# MPPC_amp.net
KiCad netlist of a schematic drawn in EAGLE
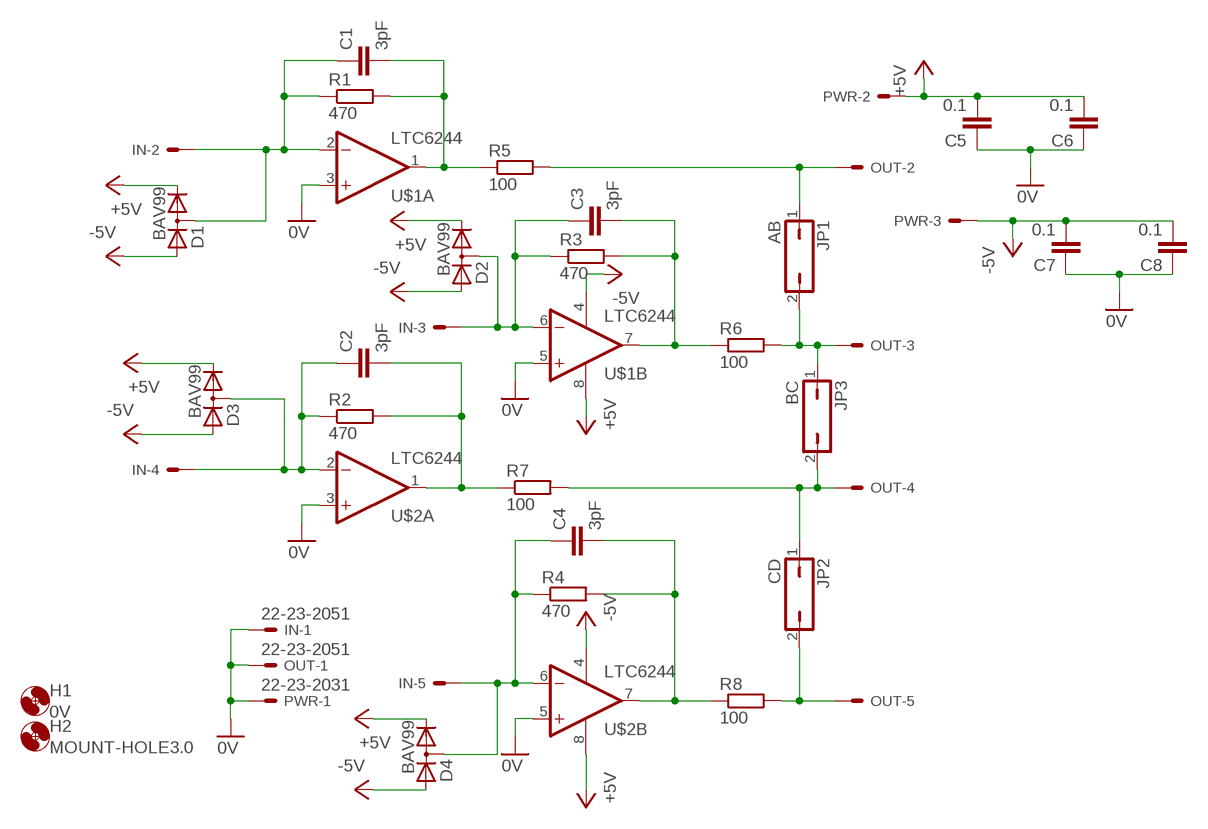
[diagram p0: schematic, sheet 1]

(export (version "E")
  (design (tool "Eeschema 10.0.6"))
  (components
    (comp (ref "C1")
      (value "3pF")
      (footprint "eagle-import:C0805")
      (libsource (lib "eagle-import") (part "C-EUC0805"))
    )
    (comp (ref "C2")
      (value "3pF")
      (footprint "eagle-import:C0805")
      (libsource (lib "eagle-import") (part "C-EUC0805"))
    )
    (comp (ref "C3")
      (value "3pF")
      (footprint "eagle-import:C0805")
      (libsource (lib "eagle-import") (part "C-EUC0805"))
    )
    (comp (ref "C4")
      (value "3pF")
      (footprint "eagle-import:C0805")
      (libsource (lib "eagle-import") (part "C-EUC0805"))
    )
    (comp (ref "C5")
      (value "0.1")
      (footprint "eagle-import:C0805")
      (libsource (lib "eagle-import") (part "C-EUC0805"))
    )
    (comp (ref "C6")
      (value "0.1")
      (footprint "eagle-import:C0805")
      (libsource (lib "eagle-import") (part "C-EUC0805"))
    )
    (comp (ref "C7")
      (value "0.1")
      (footprint "eagle-import:C0805")
      (libsource (lib "eagle-import") (part "C-EUC0805"))
    )
    (comp (ref "C8")
      (value "0.1")
      (footprint "eagle-import:C0805")
      (libsource (lib "eagle-import") (part "C-EUC0805"))
    )
    (comp (ref "D1")
      (value "BAV99")
      (footprint "eagle-import:SOT23")
      (libsource (lib "eagle-import") (part "BAV99"))
    )
    (comp (ref "D2")
      (value "BAV99")
      (footprint "eagle-import:SOT23")
      (libsource (lib "eagle-import") (part "BAV99"))
    )
    (comp (ref "D3")
      (value "BAV99")
      (footprint "eagle-import:SOT23")
      (libsource (lib "eagle-import") (part "BAV99"))
    )
    (comp (ref "D4")
      (value "BAV99")
      (footprint "eagle-import:SOT23")
      (libsource (lib "eagle-import") (part "BAV99"))
    )
    (comp (ref "H1")
      (value "0V")
      (footprint "eagle-import:3,0")
      (libsource (lib "eagle-import") (part "MOUNT-HOLE3.0"))
    )
    (comp (ref "H2")
      (value "MOUNT-HOLE3.0")
      (footprint "eagle-import:3,0")
      (libsource (lib "eagle-import") (part "MOUNT-HOLE3.0"))
    )
    (comp (ref "IN")
      (value "22-23-2051")
      (footprint "eagle-import:22-23-2051")
      (fields (field (name "MF") "MOLEX"))
      (libsource (lib "eagle-import") (part "22-23-2051"))
    )
    (comp (ref "JP1")
      (value "AB")
      (footprint "eagle-import:JP1")
      (libsource (lib "eagle-import") (part "JP1Q"))
    )
    (comp (ref "JP2")
      (value "CD")
      (footprint "eagle-import:JP1")
      (libsource (lib "eagle-import") (part "JP1Q"))
    )
    (comp (ref "JP3")
      (value "BC")
      (footprint "eagle-import:JP1")
      (libsource (lib "eagle-import") (part "JP1Q"))
    )
    (comp (ref "OUT")
      (value "22-23-2051")
      (footprint "eagle-import:22-23-2051")
      (fields (field (name "MF") "MOLEX"))
      (libsource (lib "eagle-import") (part "22-23-2051"))
    )
    (comp (ref "PWR")
      (value "22-23-2031")
      (footprint "eagle-import:22-23-2031")
      (fields (field (name "MF") "MOLEX"))
      (libsource (lib "eagle-import") (part "22-23-2031"))
    )
    (comp (ref "R1")
      (value "470")
      (footprint "eagle-import:R0805")
      (libsource (lib "eagle-import") (part "R-EU_R0805"))
    )
    (comp (ref "R2")
      (value "470")
      (footprint "eagle-import:R0805")
      (libsource (lib "eagle-import") (part "R-EU_R0805"))
    )
    (comp (ref "R3")
      (value "470")
      (footprint "eagle-import:R0805")
      (libsource (lib "eagle-import") (part "R-EU_R0805"))
    )
    (comp (ref "R4")
      (value "470")
      (footprint "eagle-import:R0805")
      (libsource (lib "eagle-import") (part "R-EU_R0805"))
    )
    (comp (ref "R5")
      (value "100")
      (footprint "eagle-import:R0805")
      (libsource (lib "eagle-import") (part "R-EU_R0805"))
    )
    (comp (ref "R6")
      (value "100")
      (footprint "eagle-import:R0805")
      (libsource (lib "eagle-import") (part "R-EU_R0805"))
    )
    (comp (ref "R7")
      (value "100")
      (footprint "eagle-import:R0805")
      (libsource (lib "eagle-import") (part "R-EU_R0805"))
    )
    (comp (ref "R8")
      (value "100")
      (footprint "eagle-import:R0805")
      (libsource (lib "eagle-import") (part "R-EU_R0805"))
    )
    (comp (ref "U$1")
      (value "LTC6244")
      (footprint "eagle-import:MSOP08")
      (libsource (lib "eagle-import") (part "LTC6244"))
    )
    (comp (ref "U$2")
      (value "LTC6244")
      (footprint "eagle-import:MSOP08")
      (libsource (lib "eagle-import") (part "LTC6244"))
    )
  )
  (nets
    (net (code "1") (name "+5V") (class "Default")
      (node (ref "C5") (pin "2") (pinfunction "2_2") (pintype "passive"))
      (node (ref "C6") (pin "2") (pinfunction "2_2") (pintype "passive"))
      (node (ref "D1") (pin "2") (pinfunction "C_2") (pintype "passive"))
      (node (ref "D2") (pin "2") (pinfunction "C_2") (pintype "passive"))
      (node (ref "D3") (pin "2") (pinfunction "C_2") (pintype "passive"))
      (node (ref "D4") (pin "2") (pinfunction "C_2") (pintype "passive"))
      (node (ref "PWR") (pin "2") (pinfunction "S_2") (pintype "passive"))
      (node (ref "U$1") (pin "8") (pinfunction "V+_8") (pintype "power_in"))
      (node (ref "U$2") (pin "8") (pinfunction "V+_8") (pintype "power_in"))
    )
    (net (code "2") (name "-5V") (class "Default")
      (node (ref "C7") (pin "2") (pinfunction "2_2") (pintype "passive"))
      (node (ref "C8") (pin "2") (pinfunction "2_2") (pintype "passive"))
      (node (ref "D1") (pin "1") (pinfunction "A_1") (pintype "passive"))
      (node (ref "D2") (pin "1") (pinfunction "A_1") (pintype "passive"))
      (node (ref "D3") (pin "1") (pinfunction "A_1") (pintype "passive"))
      (node (ref "D4") (pin "1") (pinfunction "A_1") (pintype "passive"))
      (node (ref "PWR") (pin "3") (pinfunction "S_3") (pintype "passive"))
      (node (ref "U$1") (pin "4") (pinfunction "V-_4") (pintype "power_in"))
      (node (ref "U$2") (pin "4") (pinfunction "V-_4") (pintype "power_in"))
    )
    (net (code "3") (name "0V") (class "Default")
      (node (ref "C5") (pin "1") (pinfunction "1_1") (pintype "passive"))
      (node (ref "C6") (pin "1") (pinfunction "1_1") (pintype "passive"))
      (node (ref "C7") (pin "1") (pinfunction "1_1") (pintype "passive"))
      (node (ref "C8") (pin "1") (pinfunction "1_1") (pintype "passive"))
      (node (ref "IN") (pin "1") (pinfunction "S_1") (pintype "passive"))
      (node (ref "OUT") (pin "1") (pinfunction "S_1") (pintype "passive"))
      (node (ref "PWR") (pin "1") (pinfunction "S_1") (pintype "passive"))
      (node (ref "U$1") (pin "3") (pinfunction "+IN_3") (pintype "input"))
      (node (ref "U$1") (pin "5") (pinfunction "+IN_5") (pintype "input"))
      (node (ref "U$2") (pin "3") (pinfunction "+IN_3") (pintype "input"))
      (node (ref "U$2") (pin "5") (pinfunction "+IN_5") (pintype "input"))
    )
    (net (code "4") (name "Net-(D1-AC)") (class "Default")
      (node (ref "C1") (pin "1") (pinfunction "1_1") (pintype "passive"))
      (node (ref "D1") (pin "3") (pinfunction "AC_3") (pintype "passive"))
      (node (ref "IN") (pin "2") (pinfunction "S_2") (pintype "passive"))
      (node (ref "R1") (pin "1") (pinfunction "1_1") (pintype "passive"))
      (node (ref "U$1") (pin "2") (pinfunction "-IN_2") (pintype "input"))
    )
    (net (code "5") (name "Net-(D2-AC)") (class "Default")
      (node (ref "C3") (pin "1") (pinfunction "1_1") (pintype "passive"))
      (node (ref "D2") (pin "3") (pinfunction "AC_3") (pintype "passive"))
      (node (ref "IN") (pin "3") (pinfunction "S_3") (pintype "passive"))
      (node (ref "R3") (pin "1") (pinfunction "1_1") (pintype "passive"))
      (node (ref "U$1") (pin "6") (pinfunction "-IN_6") (pintype "input"))
    )
    (net (code "6") (name "Net-(D3-AC)") (class "Default")
      (node (ref "C2") (pin "1") (pinfunction "1_1") (pintype "passive"))
      (node (ref "D3") (pin "3") (pinfunction "AC_3") (pintype "passive"))
      (node (ref "IN") (pin "4") (pinfunction "S_4") (pintype "passive"))
      (node (ref "R2") (pin "1") (pinfunction "1_1") (pintype "passive"))
      (node (ref "U$2") (pin "2") (pinfunction "-IN_2") (pintype "input"))
    )
    (net (code "7") (name "Net-(D4-AC)") (class "Default")
      (node (ref "C4") (pin "1") (pinfunction "1_1") (pintype "passive"))
      (node (ref "D4") (pin "3") (pinfunction "AC_3") (pintype "passive"))
      (node (ref "IN") (pin "5") (pinfunction "S_5") (pintype "passive"))
      (node (ref "R4") (pin "1") (pinfunction "1_1") (pintype "passive"))
      (node (ref "U$2") (pin "6") (pinfunction "-IN_6") (pintype "input"))
    )
    (net (code "8") (name "Net-(OUTB-S)") (class "Default")
      (node (ref "JP1") (pin "1") (pinfunction "1_1") (pintype "passive"))
      (node (ref "OUT") (pin "2") (pinfunction "S_2") (pintype "passive"))
      (node (ref "R5") (pin "2") (pinfunction "2_2") (pintype "passive"))
    )
    (net (code "9") (name "Net-(OUTC-S)") (class "Default")
      (node (ref "JP1") (pin "2") (pinfunction "2_2") (pintype "passive"))
      (node (ref "JP3") (pin "1") (pinfunction "1_1") (pintype "passive"))
      (node (ref "OUT") (pin "3") (pinfunction "S_3") (pintype "passive"))
      (node (ref "R6") (pin "2") (pinfunction "2_2") (pintype "passive"))
    )
    (net (code "10") (name "Net-(OUTD-S)") (class "Default")
      (node (ref "JP2") (pin "1") (pinfunction "1_1") (pintype "passive"))
      (node (ref "JP3") (pin "2") (pinfunction "2_2") (pintype "passive"))
      (node (ref "OUT") (pin "4") (pinfunction "S_4") (pintype "passive"))
      (node (ref "R7") (pin "2") (pinfunction "2_2") (pintype "passive"))
    )
    (net (code "11") (name "Net-(OUTE-S)") (class "Default")
      (node (ref "JP2") (pin "2") (pinfunction "2_2") (pintype "passive"))
      (node (ref "OUT") (pin "5") (pinfunction "S_5") (pintype "passive"))
      (node (ref "R8") (pin "2") (pinfunction "2_2") (pintype "passive"))
    )
    (net (code "12") (name "Net-(U$1A-OUT)") (class "Default")
      (node (ref "C1") (pin "2") (pinfunction "2_2") (pintype "passive"))
      (node (ref "R1") (pin "2") (pinfunction "2_2") (pintype "passive"))
      (node (ref "R5") (pin "1") (pinfunction "1_1") (pintype "passive"))
      (node (ref "U$1") (pin "1") (pinfunction "OUT_1") (pintype "output"))
    )
    (net (code "13") (name "Net-(U$1B-OUT)") (class "Default")
      (node (ref "C3") (pin "2") (pinfunction "2_2") (pintype "passive"))
      (node (ref "R3") (pin "2") (pinfunction "2_2") (pintype "passive"))
      (node (ref "R6") (pin "1") (pinfunction "1_1") (pintype "passive"))
      (node (ref "U$1") (pin "7") (pinfunction "OUT_7") (pintype "output"))
    )
    (net (code "14") (name "Net-(U$2A-OUT)") (class "Default")
      (node (ref "C2") (pin "2") (pinfunction "2_2") (pintype "passive"))
      (node (ref "R2") (pin "2") (pinfunction "2_2") (pintype "passive"))
      (node (ref "R7") (pin "1") (pinfunction "1_1") (pintype "passive"))
      (node (ref "U$2") (pin "1") (pinfunction "OUT_1") (pintype "output"))
    )
    (net (code "15") (name "Net-(U$2B-OUT)") (class "Default")
      (node (ref "C4") (pin "2") (pinfunction "2_2") (pintype "passive"))
      (node (ref "R4") (pin "2") (pinfunction "2_2") (pintype "passive"))
      (node (ref "R8") (pin "1") (pinfunction "1_1") (pintype "passive"))
      (node (ref "U$2") (pin "7") (pinfunction "OUT_7") (pintype "output"))
    )
  )
)
